# lcd.net
KiCad netlist of a schematic drawn in Altium Designer
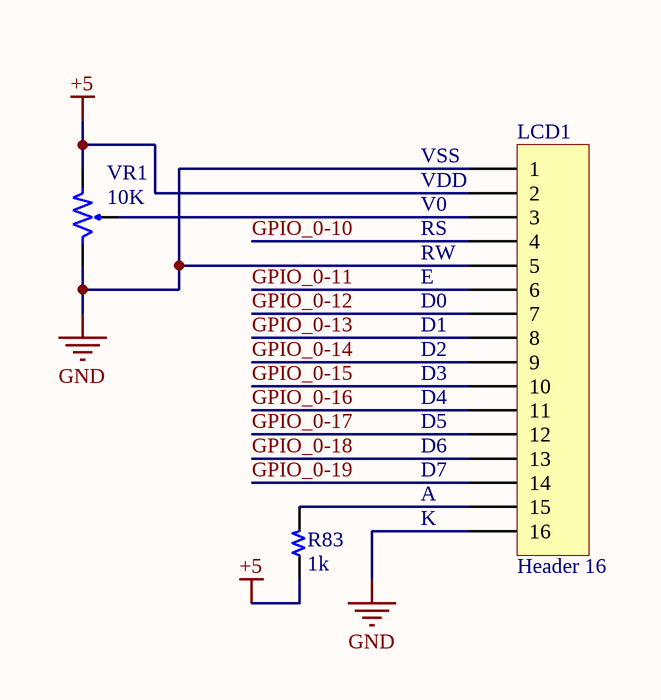
[diagram p0: lcd.SchDoc]

(export (version "E")
  (design (tool "Eeschema 10.0.6"))
  (components
    (comp (ref "LCD1")
      (value "Header 16")
      (footprint "HDR1X16")
      (description "Header, 16-Pin")
      (fields (field (name "PUBLISHER") "Altium Limited"))
      (libsource (lib "My library altium") (part "Header 16"))
    )
    (comp (ref "R83")
      (value "1k")
      (footprint "R 0603")
      (description "Resistor")
      (libsource (lib "chipfc_libs") (part "Resistor"))
    )
    (comp (ref "VR1")
      (value "10K")
      (footprint "VR1")
      (description "Var Resistor")
      (libsource (lib "syhaunguyen") (part "VR1"))
    )
  )
  (nets
    (net (code "1") (name "+5") (class "Default")
      (node (ref "LCD1") (pin "2") (pinfunction "2_2") (pintype "passive"))
      (node (ref "R83") (pin "1") (pinfunction "1_1") (pintype "passive"))
      (node (ref "VR1") (pin "1") (pinfunction "1_1") (pintype "passive"))
    )
    (net (code "2") (name "/GPIO_0-10") (class "Default")
      (node (ref "LCD1") (pin "4") (pinfunction "4_4") (pintype "passive"))
    )
    (net (code "3") (name "/GPIO_0-11") (class "Default")
      (node (ref "LCD1") (pin "6") (pinfunction "6_6") (pintype "passive"))
    )
    (net (code "4") (name "/GPIO_0-12") (class "Default")
      (node (ref "LCD1") (pin "7") (pinfunction "7_7") (pintype "passive"))
    )
    (net (code "5") (name "/GPIO_0-13") (class "Default")
      (node (ref "LCD1") (pin "8") (pinfunction "8_8") (pintype "passive"))
    )
    (net (code "6") (name "/GPIO_0-14") (class "Default")
      (node (ref "LCD1") (pin "9") (pinfunction "9_9") (pintype "passive"))
    )
    (net (code "7") (name "/GPIO_0-15") (class "Default")
      (node (ref "LCD1") (pin "10") (pinfunction "10_10") (pintype "passive"))
    )
    (net (code "8") (name "/GPIO_0-16") (class "Default")
      (node (ref "LCD1") (pin "11") (pinfunction "11_11") (pintype "passive"))
    )
    (net (code "9") (name "/GPIO_0-17") (class "Default")
      (node (ref "LCD1") (pin "12") (pinfunction "12_12") (pintype "passive"))
    )
    (net (code "10") (name "/GPIO_0-18") (class "Default")
      (node (ref "LCD1") (pin "13") (pinfunction "13_13") (pintype "passive"))
    )
    (net (code "11") (name "/GPIO_0-19") (class "Default")
      (node (ref "LCD1") (pin "14") (pinfunction "14_14") (pintype "passive"))
    )
    (net (code "12") (name "GND") (class "Default")
      (node (ref "LCD1") (pin "1") (pinfunction "1_1") (pintype "passive"))
      (node (ref "LCD1") (pin "16") (pinfunction "16_16") (pintype "passive"))
      (node (ref "LCD1") (pin "5") (pinfunction "5_5") (pintype "passive"))
      (node (ref "VR1") (pin "3") (pinfunction "3_3") (pintype "passive"))
    )
    (net (code "13") (name "Net-(LCD1-Pad3)") (class "Default")
      (node (ref "LCD1") (pin "3") (pinfunction "3_3") (pintype "passive"))
      (node (ref "VR1") (pin "2") (pinfunction "2_2") (pintype "passive"))
    )
    (net (code "14") (name "Net-(LCD1-Pad15)") (class "Default")
      (node (ref "LCD1") (pin "15") (pinfunction "15_15") (pintype "passive"))
      (node (ref "R83") (pin "2") (pinfunction "2_2") (pintype "passive"))
    )
  )
)
